# Main.net
KiCad netlist of a schematic drawn in EAGLE
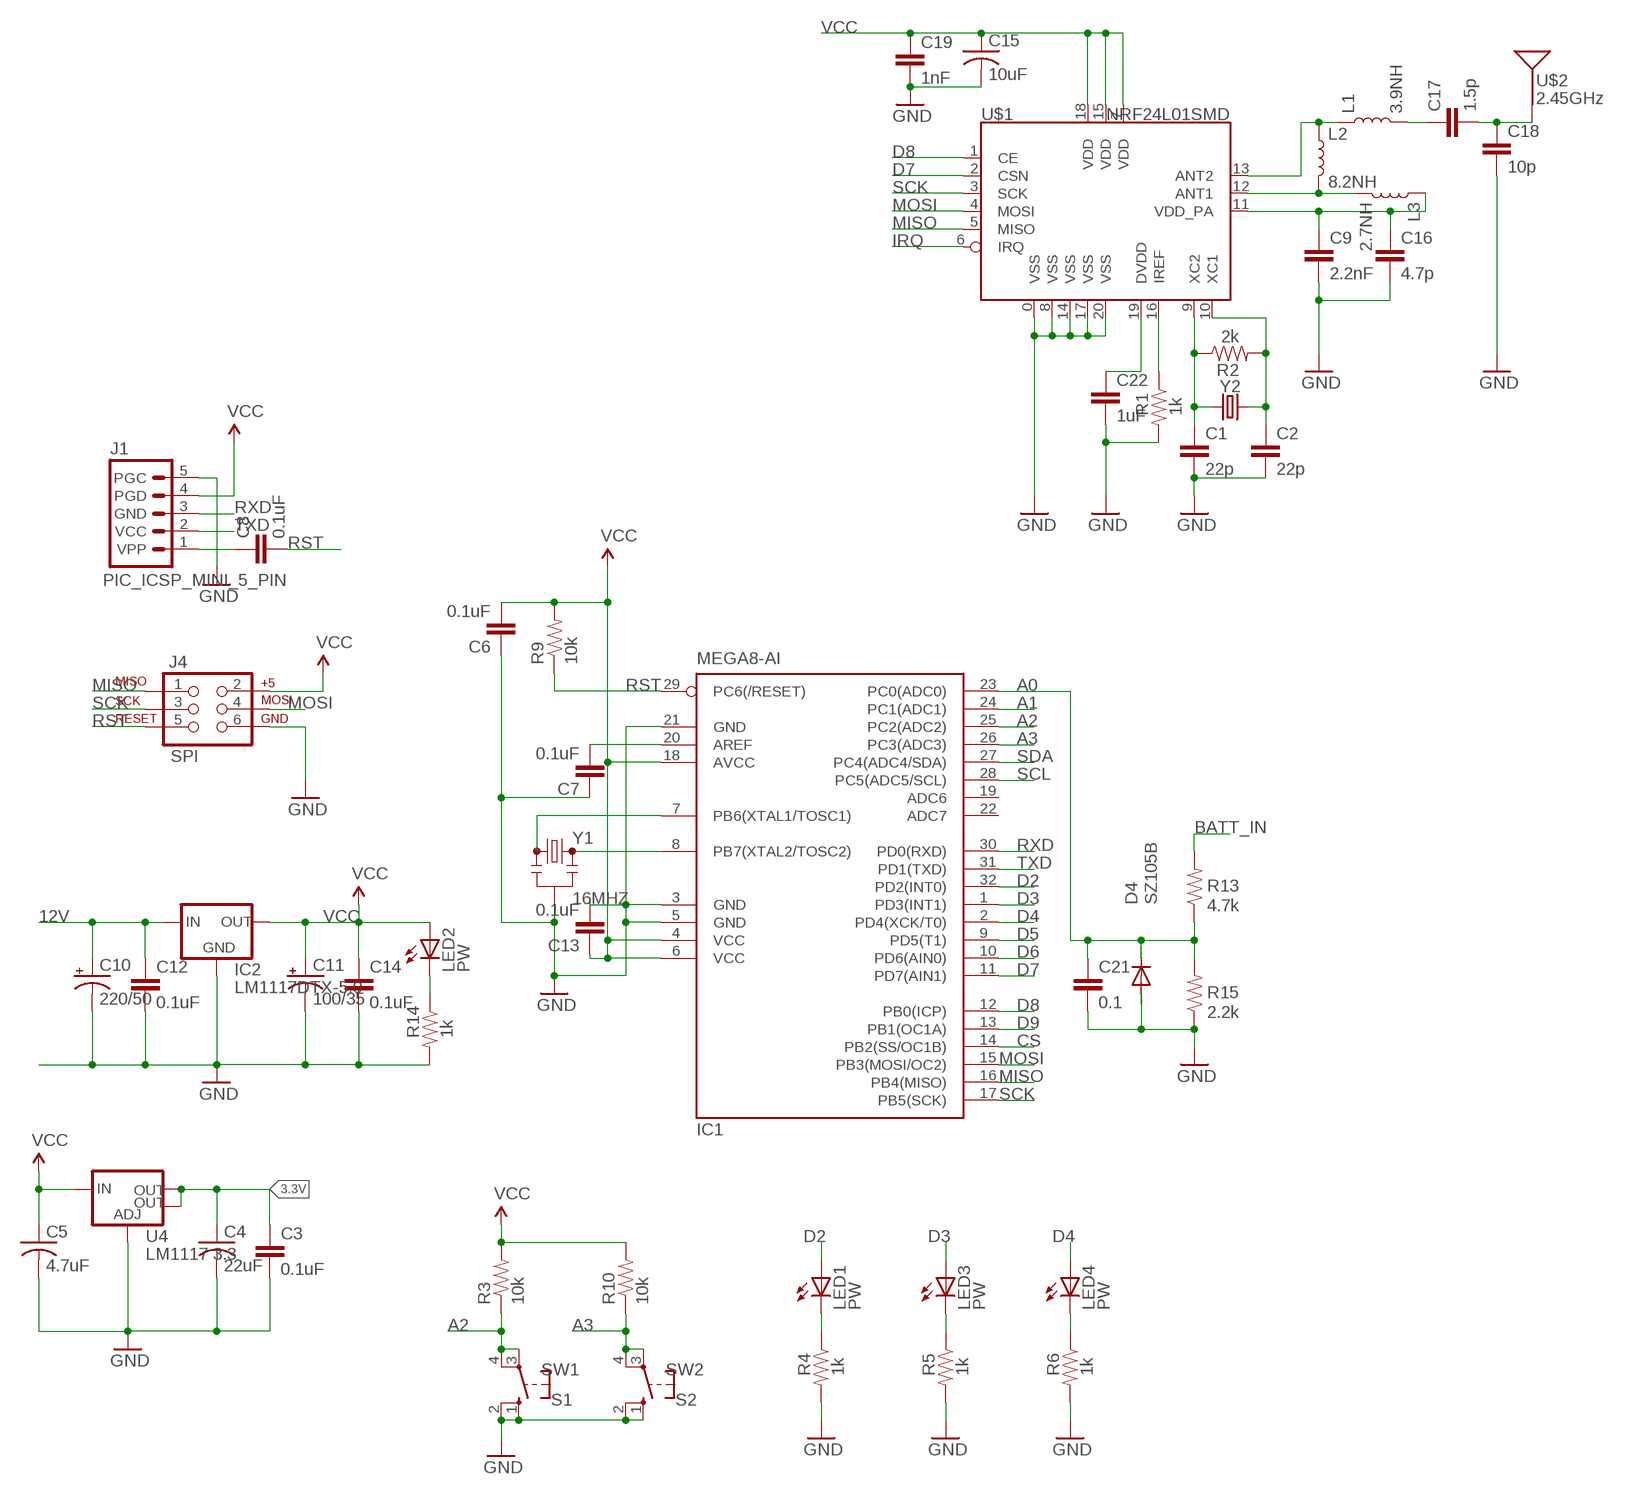
[diagram p0: schematic, sheet 1]

(export (version "E")
  (design (tool "Eeschema 10.0.6"))
  (components
    (comp (ref "C1")
      (value "22p")
      (footprint "eagle-import:0805")
      (libsource (lib "eagle-import") (part "CAP0805"))
    )
    (comp (ref "C2")
      (value "22p")
      (footprint "eagle-import:0805")
      (libsource (lib "eagle-import") (part "CAP0805"))
    )
    (comp (ref "C3")
      (value "0.1uF")
      (footprint "eagle-import:0805")
      (libsource (lib "eagle-import") (part "CAP0805"))
    )
    (comp (ref "C4")
      (value "22uF")
      (footprint "eagle-import:C1206")
      (libsource (lib "eagle-import") (part "C-USC1206"))
    )
    (comp (ref "C5")
      (value "4.7uF")
      (footprint "eagle-import:C1206")
      (libsource (lib "eagle-import") (part "C-USC1206"))
    )
    (comp (ref "C6")
      (value "0.1uF")
      (footprint "eagle-import:0805")
      (libsource (lib "eagle-import") (part "CAP0805"))
    )
    (comp (ref "C7")
      (value "0.1uF")
      (footprint "eagle-import:0805")
      (libsource (lib "eagle-import") (part "CAP0805"))
    )
    (comp (ref "C8")
      (value "0.1uF")
      (footprint "eagle-import:0805")
      (libsource (lib "eagle-import") (part "CAP0805"))
    )
    (comp (ref "C9")
      (value "2.2nF")
      (footprint "eagle-import:0805")
      (libsource (lib "eagle-import") (part "CAP0805"))
    )
    (comp (ref "C10")
      (value "220/50")
      (footprint "eagle-import:153CLV-1010")
      (libsource (lib "eagle-import") (part "CPOL-US153CLV-1010"))
    )
    (comp (ref "C11")
      (value "100/35")
      (footprint "eagle-import:153CLV-0605")
      (libsource (lib "eagle-import") (part "CPOL-US153CLV-0605"))
    )
    (comp (ref "C12")
      (value "0.1uF")
      (footprint "eagle-import:0805")
      (libsource (lib "eagle-import") (part "CAP0805"))
    )
    (comp (ref "C13")
      (value "0.1uF")
      (footprint "eagle-import:0805")
      (libsource (lib "eagle-import") (part "CAP0805"))
    )
    (comp (ref "C14")
      (value "0.1uF")
      (footprint "eagle-import:0805")
      (libsource (lib "eagle-import") (part "CAP0805"))
    )
    (comp (ref "C15")
      (value "10uF")
      (footprint "eagle-import:C1206")
      (libsource (lib "eagle-import") (part "C-USC1206"))
    )
    (comp (ref "C16")
      (value "4.7p")
      (footprint "eagle-import:0805")
      (libsource (lib "eagle-import") (part "CAP0805"))
    )
    (comp (ref "C17")
      (value "1.5p")
      (footprint "eagle-import:0805")
      (libsource (lib "eagle-import") (part "CAP0805"))
    )
    (comp (ref "C18")
      (value "10p")
      (footprint "eagle-import:0805")
      (libsource (lib "eagle-import") (part "CAP0805"))
    )
    (comp (ref "C19")
      (value "1nF")
      (footprint "eagle-import:0805")
      (libsource (lib "eagle-import") (part "CAP0805"))
    )
    (comp (ref "C21")
      (value "0.1")
      (footprint "eagle-import:0805")
      (libsource (lib "eagle-import") (part "CAP0805"))
    )
    (comp (ref "C22")
      (value "1uF")
      (footprint "eagle-import:0805")
      (libsource (lib "eagle-import") (part "CAP0805"))
    )
    (comp (ref "D4")
      (value "SZ105B")
      (footprint "eagle-import:DO-214AC")
      (libsource (lib "eagle-import") (part "DIODE-DO-214AC"))
    )
    (comp (ref "IC1")
      (value "MEGA8-AI")
      (footprint "eagle-import:TQFP32-08")
      (fields (field (name "MPN") "ATMEGA8-16AU"))
      (libsource (lib "eagle-import") (part "MEGA8-AI"))
    )
    (comp (ref "IC2")
      (value "LM1117DTX-5.0")
      (footprint "eagle-import:TO252")
      (libsource (lib "eagle-import") (part "LM1117DTX-3.3"))
    )
    (comp (ref "J1")
      (value "PIC_ICSP_MINI_5_PIN")
      (footprint "eagle-import:PIC_ICSP_MINI_5_PIN")
      (libsource (lib "eagle-import") (part "PIC_ICSP_MINI_5_PIN"))
    )
    (comp (ref "J4")
      (value "SPI")
      (footprint "eagle-import:2X3")
      (libsource (lib "eagle-import") (part "AVR_SPI_PRG_6PTH"))
    )
    (comp (ref "L1")
      (value "3.9NH")
      (footprint "eagle-import:0402")
      (libsource (lib "eagle-import") (part "INDUCTOR-0402-3.9NH"))
    )
    (comp (ref "L2")
      (value "8.2NH")
      (footprint "eagle-import:0402")
      (libsource (lib "eagle-import") (part "INDUCTOR-0402-3.9NH"))
    )
    (comp (ref "L3")
      (value "2.7NH")
      (footprint "eagle-import:0402")
      (libsource (lib "eagle-import") (part "INDUCTOR-0402-3.9NH"))
    )
    (comp (ref "LED1")
      (value "PW")
      (footprint "eagle-import:LED3MM")
      (libsource (lib "eagle-import") (part "LED3MM"))
    )
    (comp (ref "LED2")
      (value "PW")
      (footprint "eagle-import:LED3MM")
      (libsource (lib "eagle-import") (part "LED3MM"))
    )
    (comp (ref "LED3")
      (value "PW")
      (footprint "eagle-import:LED3MM")
      (libsource (lib "eagle-import") (part "LED3MM"))
    )
    (comp (ref "LED4")
      (value "PW")
      (footprint "eagle-import:LED3MM")
      (libsource (lib "eagle-import") (part "LED3MM"))
    )
    (comp (ref "R1")
      (value "1k")
      (footprint "eagle-import:0805")
      (libsource (lib "eagle-import") (part "RESISTOR0805-RES"))
    )
    (comp (ref "R2")
      (value "2k")
      (footprint "eagle-import:0805")
      (libsource (lib "eagle-import") (part "RESISTOR0805-RES"))
    )
    (comp (ref "R3")
      (value "10k")
      (footprint "eagle-import:0805")
      (libsource (lib "eagle-import") (part "RESISTOR0805-RES"))
    )
    (comp (ref "R4")
      (value "1k")
      (footprint "eagle-import:0805")
      (libsource (lib "eagle-import") (part "RESISTOR0805-RES"))
    )
    (comp (ref "R5")
      (value "1k")
      (footprint "eagle-import:0805")
      (libsource (lib "eagle-import") (part "RESISTOR0805-RES"))
    )
    (comp (ref "R6")
      (value "1k")
      (footprint "eagle-import:0805")
      (libsource (lib "eagle-import") (part "RESISTOR0805-RES"))
    )
    (comp (ref "R9")
      (value "10k")
      (footprint "eagle-import:0805")
      (libsource (lib "eagle-import") (part "RESISTOR0805-RES"))
    )
    (comp (ref "R10")
      (value "10k")
      (footprint "eagle-import:0805")
      (libsource (lib "eagle-import") (part "RESISTOR0805-RES"))
    )
    (comp (ref "R13")
      (value "4.7k")
      (footprint "eagle-import:0805")
      (libsource (lib "eagle-import") (part "RESISTOR0805-RES"))
    )
    (comp (ref "R14")
      (value "1k")
      (footprint "eagle-import:0805")
      (libsource (lib "eagle-import") (part "RESISTOR0805-RES"))
    )
    (comp (ref "R15")
      (value "2.2k")
      (footprint "eagle-import:0805")
      (libsource (lib "eagle-import") (part "RESISTOR0805-RES"))
    )
    (comp (ref "S1")
      (value "SW1")
      (footprint "eagle-import:B3F-10XX")
      (fields
        (field (name "MPN") "B3F-1000")
        (field (name "MPN_1") "B3F-1000")
        (field (name "OC_FARNELL") "176432")
        (field (name "OC_NEWARK") "36M3542")
      )
      (libsource (lib "eagle-import") (part "10-XX"))
    )
    (comp (ref "S2")
      (value "SW2")
      (footprint "eagle-import:B3F-10XX")
      (fields
        (field (name "MPN") "B3F-1000")
        (field (name "MPN_1") "B3F-1000")
        (field (name "OC_FARNELL") "176432")
        (field (name "OC_NEWARK") "36M3542")
      )
      (libsource (lib "eagle-import") (part "10-XX"))
    )
    (comp (ref "U$1")
      (value "NRF24L01SMD")
      (footprint "eagle-import:QFN20-4X4MM")
      (libsource (lib "eagle-import") (part "NRF24L01SMD"))
    )
    (comp (ref "U$2")
      (value "2.45GHz")
      (footprint "eagle-import:ANT-2.4GHZ-6.5X2.2MM")
      (libsource (lib "eagle-import") (part "ANTENNA2.4GHZ-6.5X2.2MM"))
    )
    (comp (ref "U4")
      (value "LM1117 3.3")
      (footprint "eagle-import:SOT223")
      (libsource (lib "eagle-import") (part "V_REG_LM1117SOT223"))
    )
    (comp (ref "Y1")
      (value "16MHZ")
      (footprint "eagle-import:RESONATOR-SMD")
      (libsource (lib "eagle-import") (part "RESONATOR16MHZ"))
    )
    (comp (ref "Y2")
      (value "CRYSTALSMD-5X3.2-4PAD")
      (footprint "eagle-import:CRYSTAL-SMD-5X3.2-4PAD")
      (libsource (lib "eagle-import") (part "CRYSTALSMD-5X3.2-4PAD"))
    )
  )
  (nets
    (net (code "1") (name "/12V") (class "Default")
      (node (ref "C10") (pin "+") (pinfunction "+_+") (pintype "passive"))
      (node (ref "C12") (pin "1") (pinfunction "1_1") (pintype "passive"))
      (node (ref "IC2") (pin "2") (pinfunction "IN_2") (pintype "input"))
    )
    (net (code "2") (name "/A0") (class "Default")
      (node (ref "C21") (pin "1") (pinfunction "1_1") (pintype "passive"))
      (node (ref "D4") (pin "C") (pinfunction "C_C") (pintype "passive"))
      (node (ref "IC1") (pin "23") (pinfunction "PC0(ADC0)_23") (pintype "bidirectional"))
      (node (ref "R13") (pin "1") (pinfunction "1_1") (pintype "passive"))
      (node (ref "R15") (pin "2") (pinfunction "2_2") (pintype "passive"))
    )
    (net (code "3") (name "/A1") (class "Default")
      (node (ref "IC1") (pin "24") (pinfunction "PC1(ADC1)_24") (pintype "bidirectional"))
    )
    (net (code "4") (name "/A2") (class "Default")
      (node (ref "IC1") (pin "25") (pinfunction "PC2(ADC2)_25") (pintype "bidirectional"))
      (node (ref "R3") (pin "1") (pinfunction "1_1") (pintype "passive"))
      (node (ref "S1") (pin "3") (pinfunction "P_3") (pintype "passive"))
      (node (ref "S1") (pin "4") (pinfunction "P1_4") (pintype "passive"))
    )
    (net (code "5") (name "/A3") (class "Default")
      (node (ref "IC1") (pin "26") (pinfunction "PC3(ADC3)_26") (pintype "bidirectional"))
      (node (ref "R10") (pin "1") (pinfunction "1_1") (pintype "passive"))
      (node (ref "S2") (pin "3") (pinfunction "P_3") (pintype "passive"))
      (node (ref "S2") (pin "4") (pinfunction "P1_4") (pintype "passive"))
    )
    (net (code "6") (name "/BATT_IN") (class "Default")
      (node (ref "R13") (pin "2") (pinfunction "2_2") (pintype "passive"))
    )
    (net (code "7") (name "/CS") (class "Default")
      (node (ref "IC1") (pin "14") (pinfunction "PB2(SS/OC1B)_14") (pintype "bidirectional"))
    )
    (net (code "8") (name "/D2") (class "Default")
      (node (ref "IC1") (pin "32") (pinfunction "PD2(INT0)_32") (pintype "bidirectional"))
      (node (ref "LED1") (pin "A") (pinfunction "A_A") (pintype "passive"))
    )
    (net (code "9") (name "/D3") (class "Default")
      (node (ref "IC1") (pin "1") (pinfunction "PD3(INT1)_1") (pintype "bidirectional"))
      (node (ref "LED3") (pin "A") (pinfunction "A_A") (pintype "passive"))
    )
    (net (code "10") (name "/D4") (class "Default")
      (node (ref "IC1") (pin "2") (pinfunction "PD4(XCK/T0)_2") (pintype "bidirectional"))
      (node (ref "LED4") (pin "A") (pinfunction "A_A") (pintype "passive"))
    )
    (net (code "11") (name "/D5") (class "Default")
      (node (ref "IC1") (pin "9") (pinfunction "PD5(T1)_9") (pintype "bidirectional"))
    )
    (net (code "12") (name "/D6") (class "Default")
      (node (ref "IC1") (pin "10") (pinfunction "PD6(AIN0)_10") (pintype "bidirectional"))
    )
    (net (code "13") (name "/D7") (class "Default")
      (node (ref "IC1") (pin "11") (pinfunction "PD7(AIN1)_11") (pintype "bidirectional"))
      (node (ref "U$1") (pin "2") (pinfunction "CSN_2") (pintype "input"))
    )
    (net (code "14") (name "/D8") (class "Default")
      (node (ref "IC1") (pin "12") (pinfunction "PB0(ICP)_12") (pintype "bidirectional"))
      (node (ref "U$1") (pin "1") (pinfunction "CE_1") (pintype "input"))
    )
    (net (code "15") (name "/D9") (class "Default")
      (node (ref "IC1") (pin "13") (pinfunction "PB1(OC1A)_13") (pintype "bidirectional"))
    )
    (net (code "16") (name "/IRQ") (class "Default")
      (node (ref "U$1") (pin "6") (pinfunction "IRQ_6") (pintype "output"))
    )
    (net (code "17") (name "/MISO") (class "Default")
      (node (ref "IC1") (pin "16") (pinfunction "PB4(MISO)_16") (pintype "bidirectional"))
      (node (ref "J4") (pin "1") (pinfunction "1_1") (pintype "passive"))
      (node (ref "U$1") (pin "5") (pinfunction "MISO_5") (pintype "output"))
    )
    (net (code "18") (name "/MOSI") (class "Default")
      (node (ref "IC1") (pin "15") (pinfunction "PB3(MOSI/OC2)_15") (pintype "bidirectional"))
      (node (ref "J4") (pin "4") (pinfunction "4_4") (pintype "passive"))
      (node (ref "U$1") (pin "4") (pinfunction "MOSI_4") (pintype "input"))
    )
    (net (code "19") (name "/RST") (class "Default")
      (node (ref "C8") (pin "2") (pinfunction "2_2") (pintype "passive"))
      (node (ref "IC1") (pin "29") (pinfunction "PC6(/RESET)_29") (pintype "bidirectional"))
      (node (ref "J4") (pin "5") (pinfunction "5_5") (pintype "passive"))
      (node (ref "R9") (pin "1") (pinfunction "1_1") (pintype "passive"))
    )
    (net (code "20") (name "/RXD") (class "Default")
      (node (ref "IC1") (pin "30") (pinfunction "PD0(RXD)_30") (pintype "bidirectional"))
      (node (ref "J1") (pin "3") (pinfunction "GND_3") (pintype "passive"))
    )
    (net (code "21") (name "/SCK") (class "Default")
      (node (ref "IC1") (pin "17") (pinfunction "PB5(SCK)_17") (pintype "bidirectional"))
      (node (ref "J4") (pin "3") (pinfunction "3_3") (pintype "passive"))
      (node (ref "U$1") (pin "3") (pinfunction "SCK_3") (pintype "input"))
    )
    (net (code "22") (name "/SCL") (class "Default")
      (node (ref "IC1") (pin "28") (pinfunction "PC5(ADC5/SCL)_28") (pintype "bidirectional"))
    )
    (net (code "23") (name "/SDA") (class "Default")
      (node (ref "IC1") (pin "27") (pinfunction "PC4(ADC4/SDA)_27") (pintype "bidirectional"))
    )
    (net (code "24") (name "/TXD") (class "Default")
      (node (ref "IC1") (pin "31") (pinfunction "PD1(TXD)_31") (pintype "bidirectional"))
      (node (ref "J1") (pin "2") (pinfunction "VCC_2") (pintype "passive"))
    )
    (net (code "25") (name "3.3V") (class "Default")
      (node (ref "C3") (pin "1") (pinfunction "1_1") (pintype "passive"))
      (node (ref "C4") (pin "1") (pinfunction "1_1") (pintype "passive"))
      (node (ref "U4") (pin "2") (pinfunction "OUT_2") (pintype "output"))
      (node (ref "U4") (pin "4") (pinfunction "OUT_4") (pintype "output"))
    )
    (net (code "26") (name "GND") (class "Default")
      (node (ref "C1") (pin "2") (pinfunction "2_2") (pintype "passive"))
      (node (ref "C10") (pin "-") (pinfunction "-_-") (pintype "passive"))
      (node (ref "C11") (pin "-") (pinfunction "-_-") (pintype "passive"))
      (node (ref "C12") (pin "2") (pinfunction "2_2") (pintype "passive"))
      (node (ref "C13") (pin "2") (pinfunction "2_2") (pintype "passive"))
      (node (ref "C14") (pin "2") (pinfunction "2_2") (pintype "passive"))
      (node (ref "C15") (pin "2") (pinfunction "2_2") (pintype "passive"))
      (node (ref "C16") (pin "2") (pinfunction "2_2") (pintype "passive"))
      (node (ref "C18") (pin "2") (pinfunction "2_2") (pintype "passive"))
      (node (ref "C19") (pin "2") (pinfunction "2_2") (pintype "passive"))
      (node (ref "C2") (pin "2") (pinfunction "2_2") (pintype "passive"))
      (node (ref "C21") (pin "2") (pinfunction "2_2") (pintype "passive"))
      (node (ref "C22") (pin "2") (pinfunction "2_2") (pintype "passive"))
      (node (ref "C3") (pin "2") (pinfunction "2_2") (pintype "passive"))
      (node (ref "C4") (pin "2") (pinfunction "2_2") (pintype "passive"))
      (node (ref "C5") (pin "2") (pinfunction "2_2") (pintype "passive"))
      (node (ref "C6") (pin "1") (pinfunction "1_1") (pintype "passive"))
      (node (ref "C7") (pin "1") (pinfunction "1_1") (pintype "passive"))
      (node (ref "C9") (pin "2") (pinfunction "2_2") (pintype "passive"))
      (node (ref "D4") (pin "A") (pinfunction "A_A") (pintype "passive"))
      (node (ref "IC1") (pin "21") (pinfunction "GND_21") (pintype "power_in"))
      (node (ref "IC1") (pin "3") (pinfunction "GND_3") (pintype "power_in"))
      (node (ref "IC1") (pin "5") (pinfunction "GND_5") (pintype "power_in"))
      (node (ref "IC2") (pin "1") (pinfunction "GND_1") (pintype "input"))
      (node (ref "J1") (pin "5") (pinfunction "PGC_5") (pintype "passive"))
      (node (ref "J4") (pin "6") (pinfunction "6_6") (pintype "passive"))
      (node (ref "R1") (pin "2") (pinfunction "2_2") (pintype "passive"))
      (node (ref "R14") (pin "2") (pinfunction "2_2") (pintype "passive"))
      (node (ref "R15") (pin "1") (pinfunction "1_1") (pintype "passive"))
      (node (ref "R4") (pin "2") (pinfunction "2_2") (pintype "passive"))
      (node (ref "R5") (pin "2") (pinfunction "2_2") (pintype "passive"))
      (node (ref "R6") (pin "2") (pinfunction "2_2") (pintype "passive"))
      (node (ref "S1") (pin "1") (pinfunction "S_1") (pintype "passive"))
      (node (ref "S1") (pin "2") (pinfunction "S1_2") (pintype "passive"))
      (node (ref "S2") (pin "1") (pinfunction "S_1") (pintype "passive"))
      (node (ref "S2") (pin "2") (pinfunction "S1_2") (pintype "passive"))
      (node (ref "U$1") (pin "0") (pinfunction "VSS_0") (pintype "power_in"))
      (node (ref "U$1") (pin "14") (pinfunction "VSS_14") (pintype "power_in"))
      (node (ref "U$1") (pin "17") (pinfunction "VSS_17") (pintype "power_in"))
      (node (ref "U$1") (pin "20") (pinfunction "VSS_20") (pintype "power_in"))
      (node (ref "U$1") (pin "8") (pinfunction "VSS_8") (pintype "power_in"))
      (node (ref "U4") (pin "1") (pinfunction "ADJ_1") (pintype "input"))
      (node (ref "Y1") (pin "2") (pinfunction "2_2") (pintype "passive"))
    )
    (net (code "27") (name "Net-(C17-Pad1)") (class "Default")
      (node (ref "C17") (pin "1") (pinfunction "1_1") (pintype "passive"))
      (node (ref "L1") (pin "2") (pinfunction "2_2") (pintype "passive"))
    )
    (net (code "28") (name "Net-(IC1-AREF)") (class "Default")
      (node (ref "C7") (pin "2") (pinfunction "2_2") (pintype "passive"))
      (node (ref "IC1") (pin "20") (pinfunction "AREF_20") (pintype "passive"))
    )
    (net (code "29") (name "Net-(IC1-PB6(XTAL1{slash}TOSC1))") (class "Default")
      (node (ref "IC1") (pin "7") (pinfunction "PB6(XTAL1/TOSC1)_7") (pintype "bidirectional"))
      (node (ref "Y1") (pin "1") (pinfunction "1_1") (pintype "passive"))
    )
    (net (code "30") (name "Net-(IC1-PB7(XTAL2{slash}TOSC2))") (class "Default")
      (node (ref "IC1") (pin "8") (pinfunction "PB7(XTAL2/TOSC2)_8") (pintype "bidirectional"))
      (node (ref "Y1") (pin "3") (pinfunction "3_3") (pintype "passive"))
    )
    (net (code "31") (name "Net-(J1-VPP)") (class "Default")
      (node (ref "C8") (pin "1") (pinfunction "1_1") (pintype "passive"))
      (node (ref "J1") (pin "1") (pinfunction "VPP_1") (pintype "passive"))
    )
    (net (code "32") (name "Net-(LED1-C)") (class "Default")
      (node (ref "LED1") (pin "K") (pinfunction "C_K") (pintype "passive"))
      (node (ref "R4") (pin "1") (pinfunction "1_1") (pintype "passive"))
    )
    (net (code "33") (name "Net-(LED2-C)") (class "Default")
      (node (ref "LED2") (pin "K") (pinfunction "C_K") (pintype "passive"))
      (node (ref "R14") (pin "1") (pinfunction "1_1") (pintype "passive"))
    )
    (net (code "34") (name "Net-(LED3-C)") (class "Default")
      (node (ref "LED3") (pin "K") (pinfunction "C_K") (pintype "passive"))
      (node (ref "R5") (pin "1") (pinfunction "1_1") (pintype "passive"))
    )
    (net (code "35") (name "Net-(LED4-C)") (class "Default")
      (node (ref "LED4") (pin "K") (pinfunction "C_K") (pintype "passive"))
      (node (ref "R6") (pin "1") (pinfunction "1_1") (pintype "passive"))
    )
    (net (code "36") (name "Net-(U$1-ANT1)") (class "Default")
      (node (ref "L2") (pin "2") (pinfunction "2_2") (pintype "passive"))
      (node (ref "L3") (pin "2") (pinfunction "2_2") (pintype "passive"))
      (node (ref "U$1") (pin "12") (pinfunction "ANT1_12") (pintype "output"))
    )
    (net (code "37") (name "Net-(U$1-ANT2)") (class "Default")
      (node (ref "L1") (pin "1") (pinfunction "1_1") (pintype "passive"))
      (node (ref "L2") (pin "1") (pinfunction "1_1") (pintype "passive"))
      (node (ref "U$1") (pin "13") (pinfunction "ANT2_13") (pintype "output"))
    )
    (net (code "38") (name "Net-(U$1-DVDD)") (class "Default")
      (node (ref "C22") (pin "1") (pinfunction "1_1") (pintype "passive"))
      (node (ref "U$1") (pin "19") (pinfunction "DVDD_19") (pintype "power_in"))
    )
    (net (code "39") (name "Net-(U$1-IREF)") (class "Default")
      (node (ref "R1") (pin "1") (pinfunction "1_1") (pintype "passive"))
      (node (ref "U$1") (pin "16") (pinfunction "IREF_16") (pintype "input"))
    )
    (net (code "40") (name "Net-(U$1-VDD_PA)") (class "Default")
      (node (ref "C16") (pin "1") (pinfunction "1_1") (pintype "passive"))
      (node (ref "C9") (pin "1") (pinfunction "1_1") (pintype "passive"))
      (node (ref "L3") (pin "1") (pinfunction "1_1") (pintype "passive"))
      (node (ref "U$1") (pin "11") (pinfunction "VDD_PA_11") (pintype "power_in"))
    )
    (net (code "41") (name "Net-(U$1-XC1)") (class "Default")
      (node (ref "C2") (pin "1") (pinfunction "1_1") (pintype "passive"))
      (node (ref "R2") (pin "2") (pinfunction "2_2") (pintype "passive"))
      (node (ref "U$1") (pin "10") (pinfunction "XC1_10") (pintype "input"))
      (node (ref "Y2") (pin "3") (pinfunction "2_3") (pintype "passive"))
    )
    (net (code "42") (name "Net-(U$1-XC2)") (class "Default")
      (node (ref "C1") (pin "1") (pinfunction "1_1") (pintype "passive"))
      (node (ref "R2") (pin "1") (pinfunction "1_1") (pintype "passive"))
      (node (ref "U$1") (pin "9") (pinfunction "XC2_9") (pintype "input"))
      (node (ref "Y2") (pin "1") (pinfunction "1_1") (pintype "passive"))
    )
    (net (code "43") (name "Net-(U$2-SIGNAL)") (class "Default")
      (node (ref "C17") (pin "2") (pinfunction "2_2") (pintype "passive"))
      (node (ref "C18") (pin "1") (pinfunction "1_1") (pintype "passive"))
      (node (ref "U$2") (pin "FEED") (pinfunction "SIGNAL_FEED") (pintype "bidirectional"))
    )
    (net (code "44") (name "VCC") (class "Default")
      (node (ref "C11") (pin "+") (pinfunction "+_+") (pintype "passive"))
      (node (ref "C13") (pin "1") (pinfunction "1_1") (pintype "passive"))
      (node (ref "C14") (pin "1") (pinfunction "1_1") (pintype "passive"))
      (node (ref "C15") (pin "1") (pinfunction "1_1") (pintype "passive"))
      (node (ref "C19") (pin "1") (pinfunction "1_1") (pintype "passive"))
      (node (ref "C5") (pin "1") (pinfunction "1_1") (pintype "passive"))
      (node (ref "C6") (pin "2") (pinfunction "2_2") (pintype "passive"))
      (node (ref "IC1") (pin "18") (pinfunction "AVCC_18") (pintype "power_in"))
      (node (ref "IC1") (pin "4") (pinfunction "VCC_4") (pintype "power_in"))
      (node (ref "IC1") (pin "6") (pinfunction "VCC_6") (pintype "power_in"))
      (node (ref "IC2") (pin "TAB") (pinfunction "OUT_TAB") (pintype "passive"))
      (node (ref "J1") (pin "4") (pinfunction "PGD_4") (pintype "passive"))
      (node (ref "J4") (pin "2") (pinfunction "2_2") (pintype "passive"))
      (node (ref "LED2") (pin "A") (pinfunction "A_A") (pintype "passive"))
      (node (ref "R10") (pin "2") (pinfunction "2_2") (pintype "passive"))
      (node (ref "R3") (pin "2") (pinfunction "2_2") (pintype "passive"))
      (node (ref "R9") (pin "2") (pinfunction "2_2") (pintype "passive"))
      (node (ref "U$1") (pin "15") (pinfunction "VDD_15") (pintype "power_in"))
      (node (ref "U$1") (pin "18") (pinfunction "VDD_18") (pintype "power_in"))
      (node (ref "U$1") (pin "7") (pinfunction "VDD_7") (pintype "power_in"))
      (node (ref "U4") (pin "3") (pinfunction "IN_3") (pintype "input"))
    )
    (net (code "45") (name "unconnected-(IC1-ADC6-Pad19)") (class "Default")
      (node (ref "IC1") (pin "19") (pinfunction "ADC6_19") (pintype "bidirectional"))
    )
    (net (code "46") (name "unconnected-(IC1-ADC7-Pad22)") (class "Default")
      (node (ref "IC1") (pin "22") (pinfunction "ADC7_22") (pintype "bidirectional"))
    )
  )
)
